# ATMEGA328P.net
KiCad netlist of a schematic drawn in Altium Designer
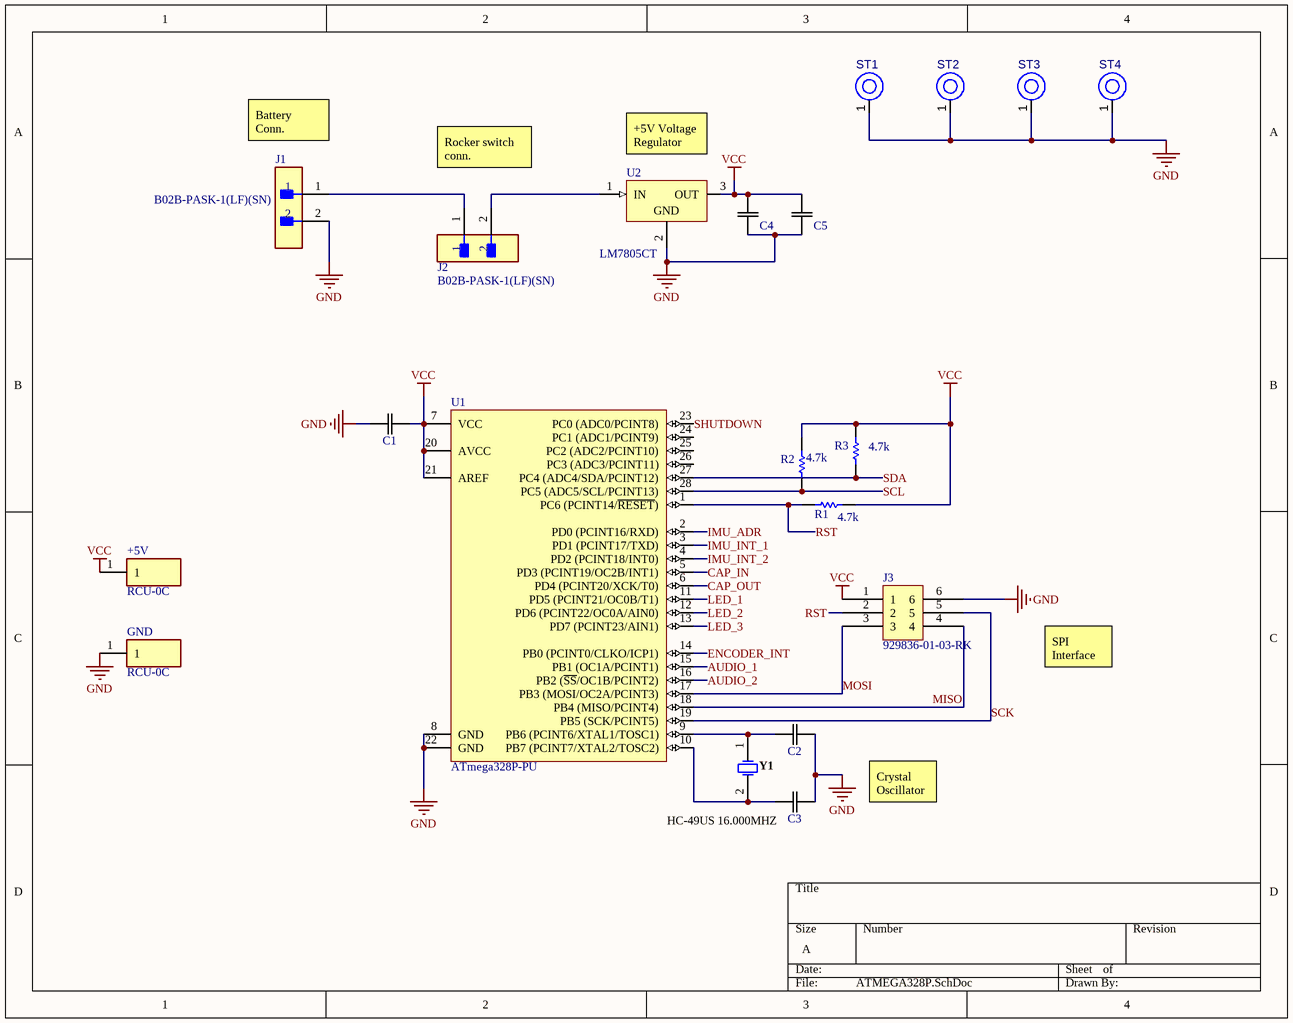
[diagram p0: ATMEGA328P.SchDoc]

(export (version "E")
  (design (tool "Eeschema 10.0.6"))
  (components
    (comp (ref "+5V")
      (value "RCU-0C")
      (footprint "TP+195X110")
      (description "Natural PC Test Point - - Plating Surface Mount Mounting Type")
      (fields (field (name "MF") "TE Connectivity AMP Connectors"))
      (libsource (lib "RCU-0C") (part "RCU-0C"))
    )
    (comp (ref "C1")
      (value "Cap, 22pF, ceramic, TH")
      (footprint "New footprint 1")
      (libsource (lib "University of Pittsburgh") (part "Cap, ceramic"))
    )
    (comp (ref "C2")
      (value "Cap, 22pF, ceramic, TH")
      (footprint "New footprint 1")
      (libsource (lib "University of Pittsburgh") (part "Cap, ceramic"))
    )
    (comp (ref "C3")
      (value "Cap, 22pF, ceramic, TH")
      (footprint "New footprint 1")
      (libsource (lib "University of Pittsburgh") (part "Cap, ceramic"))
    )
    (comp (ref "C4")
      (value "Cap, 22pF, ceramic, TH")
      (footprint "New footprint 1")
      (libsource (lib "University of Pittsburgh") (part "Cap, ceramic"))
    )
    (comp (ref "C5")
      (value "Cap, 22pF, ceramic, TH")
      (footprint "New footprint 1")
      (libsource (lib "University of Pittsburgh") (part "Cap, ceramic"))
    )
    (comp (ref "GND")
      (value "RCU-0C")
      (footprint "TP+195X110")
      (description "Natural PC Test Point - - Plating Surface Mount Mounting Type")
      (fields (field (name "MF") "TE Connectivity AMP Connectors"))
      (libsource (lib "RCU-0C") (part "RCU-0C"))
    )
    (comp (ref "J1")
      (value "B02B-PASK-1(LF)(SN)")
      (footprint "FP-B02B-PASK-1_LF_SN-MFG")
      (description "CONN HEADER VERT 2POS 2MM")
      (libsource (lib "Altium Content Vault") (part "3bc925449376181038e59eaffc5286c"))
    )
    (comp (ref "J2")
      (value "B02B-PASK-1(LF)(SN)")
      (footprint "FP-B02B-PASK-1_LF_SN-MFG")
      (description "CONN HEADER VERT 2POS 2MM")
      (libsource (lib "") (part "3bc925449376181038e59eaffc5286c_1"))
    )
    (comp (ref "J3")
      (value "929836-01-03-RK")
      (footprint "929836-01-03-RK-Footprint-1")
      (description "3x2 male header")
      (libsource (lib "University of Pittsburgh") (part "929836-01-03-RK-Symbol-1"))
    )
    (comp (ref "R1")
      (value "4.7k")
      (footprint "RESA60-630X240")
      (description "RES 1K OHM 1/4W 1% AXIAL")
      (fields (field (name "TOLERANCE") "1%"))
      (libsource (lib "University of Pittsburgh") (part "RES-2"))
    )
    (comp (ref "R2")
      (value "4.7k")
      (footprint "RESA60-630X240")
      (description "RES 1K OHM 1/4W 1% AXIAL")
      (fields (field (name "TOLERANCE") "1%"))
      (libsource (lib "University of Pittsburgh") (part "RES-2"))
    )
    (comp (ref "R3")
      (value "4.7k")
      (footprint "RESA60-630X240")
      (fields (field (name "TOLERANCE") "1%"))
      (libsource (lib "University of Pittsburgh") (part "RES-2"))
    )
    (comp (ref "ST1")
      (value "PTH-M2D5X5")
      (footprint "PTH-M2D5X5")
      (description "M2 PTH (2.5mm), 5mm pad")
      (libsource (lib "University of Pittsburgh") (part "CMP-00028-00000-1"))
    )
    (comp (ref "ST2")
      (value "PTH-M2D5X5")
      (footprint "PTH-M2D5X5")
      (description "M2 PTH (2.5mm), 5mm pad")
      (libsource (lib "University of Pittsburgh") (part "CMP-00028-00000-1"))
    )
    (comp (ref "ST3")
      (value "PTH-M2D5X5")
      (footprint "PTH-M2D5X5")
      (description "M2 PTH (2.5mm), 5mm pad")
      (libsource (lib "University of Pittsburgh") (part "CMP-00028-00000-1"))
    )
    (comp (ref "ST4")
      (value "PTH-M2D5X5")
      (footprint "PTH-M2D5X5")
      (description "M2 PTH (2.5mm), 5mm pad")
      (libsource (lib "University of Pittsburgh") (part "CMP-00028-00000-1"))
    )
    (comp (ref "U1")
      (value "ATmega328P-PU")
      (footprint "28P3")
      (libsource (lib "Altium Content Vault") (part "MC-8B-ATM48-IL28"))
    )
    (comp (ref "U2")
      (value "LM7805CT")
      (footprint "FAIR-TO-220-3")
      (description "Positive Voltage Regulator, 5 V, 1 A, -40 to 125 degC, 3-Pin TO-220, RoHS, Tube")
      (fields (field (name "MANUFACTURER") "FairchildSemiconductor"))
      (libsource (lib "Altium Content Vault") (part "FAIR-LM7805CT-TO220-3"))
    )
    (comp (ref "Y1")
      (value "HC-49US 16.000MHZ")
      (footprint "JPY-HC-49US")
      (description "Crystal, 16 MHz, +/- 30 ppm, 18 pF, -20 to 70 degC, 2-Pin THD")
      (fields (field (name "MANUFACTURER") "Jing peng yuan"))
      (libsource (lib "University of Pittsburgh") (part "XTAL-1-2-2"))
    )
  )
  (nets
    (net (code "1") (name "/AUDIO_1") (class "Default")
      (node (ref "U1") (pin "15") (pinfunction "PB1_(OC1A/PCINT1)_15") (pintype "bidirectional"))
    )
    (net (code "2") (name "/AUDIO_2") (class "Default")
      (node (ref "U1") (pin "16") (pinfunction "PB2_(~{SS}/OC1B/PCINT2)_16") (pintype "bidirectional"))
    )
    (net (code "3") (name "/CAP_IN") (class "Default")
      (node (ref "U1") (pin "5") (pinfunction "PD3_(PCINT19/OC2B/INT1)_5") (pintype "bidirectional"))
    )
    (net (code "4") (name "/CAP_OUT") (class "Default")
      (node (ref "U1") (pin "6") (pinfunction "PD4_(PCINT20/XCK/T0)_6") (pintype "bidirectional"))
    )
    (net (code "5") (name "/ENCODER_INT") (class "Default")
      (node (ref "U1") (pin "14") (pinfunction "PB0_(PCINT0/CLKO/ICP1)_14") (pintype "bidirectional"))
    )
    (net (code "6") (name "/IMU_ADR") (class "Default")
      (node (ref "U1") (pin "2") (pinfunction "PD0_(PCINT16/RXD)_2") (pintype "bidirectional"))
    )
    (net (code "7") (name "/IMU_INT_1") (class "Default")
      (node (ref "U1") (pin "3") (pinfunction "PD1_(PCINT17/TXD)_3") (pintype "bidirectional"))
    )
    (net (code "8") (name "/IMU_INT_2") (class "Default")
      (node (ref "U1") (pin "4") (pinfunction "PD2_(PCINT18/INT0)_4") (pintype "bidirectional"))
    )
    (net (code "9") (name "/LED_1") (class "Default")
      (node (ref "U1") (pin "11") (pinfunction "PD5_(PCINT21/OC0B/T1)_11") (pintype "bidirectional"))
    )
    (net (code "10") (name "/LED_2") (class "Default")
      (node (ref "U1") (pin "12") (pinfunction "PD6_(PCINT22/OC0A/AIN0)_12") (pintype "bidirectional"))
    )
    (net (code "11") (name "/LED_3") (class "Default")
      (node (ref "U1") (pin "13") (pinfunction "PD7_(PCINT23/AIN1)_13") (pintype "bidirectional"))
    )
    (net (code "12") (name "/MISO") (class "Default")
      (node (ref "J3") (pin "4") (pinfunction "4_4") (pintype "passive"))
      (node (ref "U1") (pin "18") (pinfunction "PB4_(MISO/PCINT4)_18") (pintype "bidirectional"))
    )
    (net (code "13") (name "/MOSI") (class "Default")
      (node (ref "J3") (pin "3") (pinfunction "3_3") (pintype "passive"))
      (node (ref "U1") (pin "17") (pinfunction "PB3_(MOSI/OC2A/PCINT3)_17") (pintype "bidirectional"))
    )
    (net (code "14") (name "/RST") (class "Default")
      (node (ref "J3") (pin "2") (pinfunction "2_2") (pintype "passive"))
      (node (ref "R1") (pin "1") (pinfunction "1_1") (pintype "passive"))
      (node (ref "U1") (pin "1") (pinfunction "PC6_(PCINT14/~{RESET})_1") (pintype "bidirectional"))
    )
    (net (code "15") (name "/SCK") (class "Default")
      (node (ref "J3") (pin "5") (pinfunction "5_5") (pintype "passive"))
      (node (ref "U1") (pin "19") (pinfunction "PB5_(SCK/PCINT5)_19") (pintype "bidirectional"))
    )
    (net (code "16") (name "/SCL") (class "Default")
      (node (ref "R2") (pin "1") (pinfunction "1_1") (pintype "passive"))
      (node (ref "U1") (pin "28") (pinfunction "PC5_(ADC5/SCL/PCINT13)_28") (pintype "bidirectional"))
    )
    (net (code "17") (name "/SDA") (class "Default")
      (node (ref "R3") (pin "1") (pinfunction "1_1") (pintype "passive"))
      (node (ref "U1") (pin "27") (pinfunction "PC4_(ADC4/SDA/PCINT12)_27") (pintype "bidirectional"))
    )
    (net (code "18") (name "/SHUTDOWN") (class "Default")
      (node (ref "U1") (pin "23") (pinfunction "PC0_(ADC0/PCINT8)_23") (pintype "bidirectional"))
    )
    (net (code "19") (name "GND") (class "Default")
      (node (ref "C1") (pin "1") (pinfunction "1_1") (pintype "passive"))
      (node (ref "C2") (pin "2") (pinfunction "2_2") (pintype "passive"))
      (node (ref "C3") (pin "2") (pinfunction "2_2") (pintype "passive"))
      (node (ref "C4") (pin "2") (pinfunction "2_2") (pintype "passive"))
      (node (ref "C5") (pin "2") (pinfunction "2_2") (pintype "passive"))
      (node (ref "GND") (pin "1") (pinfunction "1_1") (pintype "passive"))
      (node (ref "J1") (pin "2") (pinfunction "2_2") (pintype "passive"))
      (node (ref "J3") (pin "6") (pinfunction "6_6") (pintype "passive"))
      (node (ref "ST1") (pin "1") (pinfunction "H1_1") (pintype "passive"))
      (node (ref "ST2") (pin "1") (pinfunction "H1_1") (pintype "passive"))
      (node (ref "ST3") (pin "1") (pinfunction "H1_1") (pintype "passive"))
      (node (ref "ST4") (pin "1") (pinfunction "H1_1") (pintype "passive"))
      (node (ref "U1") (pin "22") (pinfunction "GND_22") (pintype "power_in"))
      (node (ref "U1") (pin "8") (pinfunction "GND_8") (pintype "power_in"))
      (node (ref "U2") (pin "2") (pinfunction "GND_2") (pintype "power_in"))
    )
    (net (code "20") (name "Net-(J1-Pad1)") (class "Default")
      (node (ref "J1") (pin "1") (pinfunction "1_1") (pintype "passive"))
      (node (ref "J2") (pin "1") (pinfunction "1_1") (pintype "passive"))
    )
    (net (code "21") (name "Net-(U1-PB6_(PCINT6{slash}XTAL1{slash}TOSC1))") (class "Default")
      (node (ref "C2") (pin "1") (pinfunction "1_1") (pintype "passive"))
      (node (ref "U1") (pin "9") (pinfunction "PB6_(PCINT6/XTAL1/TOSC1)_9") (pintype "bidirectional"))
      (node (ref "Y1") (pin "1") (pinfunction "1_1") (pintype "passive"))
    )
    (net (code "22") (name "Net-(U1-PB7_(PCINT7{slash}XTAL2{slash}TOSC2))") (class "Default")
      (node (ref "C3") (pin "1") (pinfunction "1_1") (pintype "passive"))
      (node (ref "U1") (pin "10") (pinfunction "PB7_(PCINT7/XTAL2/TOSC2)_10") (pintype "bidirectional"))
      (node (ref "Y1") (pin "2") (pinfunction "2_2") (pintype "passive"))
    )
    (net (code "23") (name "Net-(U2-IN)") (class "Default")
      (node (ref "J2") (pin "2") (pinfunction "2_2") (pintype "passive"))
      (node (ref "U2") (pin "1") (pinfunction "IN_1") (pintype "input"))
    )
    (net (code "24") (name "VCC") (class "Default")
      (node (ref "+5V") (pin "1") (pinfunction "1_1") (pintype "passive"))
      (node (ref "C1") (pin "2") (pinfunction "2_2") (pintype "passive"))
      (node (ref "C4") (pin "1") (pinfunction "1_1") (pintype "passive"))
      (node (ref "C5") (pin "1") (pinfunction "1_1") (pintype "passive"))
      (node (ref "J3") (pin "1") (pinfunction "1_1") (pintype "passive"))
      (node (ref "R1") (pin "2") (pinfunction "2_2") (pintype "passive"))
      (node (ref "R2") (pin "2") (pinfunction "2_2") (pintype "passive"))
      (node (ref "R3") (pin "2") (pinfunction "2_2") (pintype "passive"))
      (node (ref "U1") (pin "20") (pinfunction "AVCC_20") (pintype "power_in"))
      (node (ref "U1") (pin "21") (pinfunction "AREF_21") (pintype "power_in"))
      (node (ref "U1") (pin "7") (pinfunction "VCC_7") (pintype "power_in"))
      (node (ref "U2") (pin "3") (pinfunction "OUT_3") (pintype "passive"))
    )
    (net (code "25") (name "unconnected-(U1-PC1_(ADC1{slash}PCINT9)-Pad24)") (class "Default")
      (node (ref "U1") (pin "24") (pinfunction "PC1_(ADC1/PCINT9)_24") (pintype "bidirectional"))
    )
    (net (code "26") (name "unconnected-(U1-PC2_(ADC2{slash}PCINT10)-Pad25)") (class "Default")
      (node (ref "U1") (pin "25") (pinfunction "PC2_(ADC2/PCINT10)_25") (pintype "bidirectional"))
    )
    (net (code "27") (name "unconnected-(U1-PC3_(ADC3{slash}PCINT11)-Pad26)") (class "Default")
      (node (ref "U1") (pin "26") (pinfunction "PC3_(ADC3/PCINT11)_26") (pintype "bidirectional"))
    )
  )
)
